# H_Bridge.net
KiCad netlist of a schematic drawn in Altium Designer
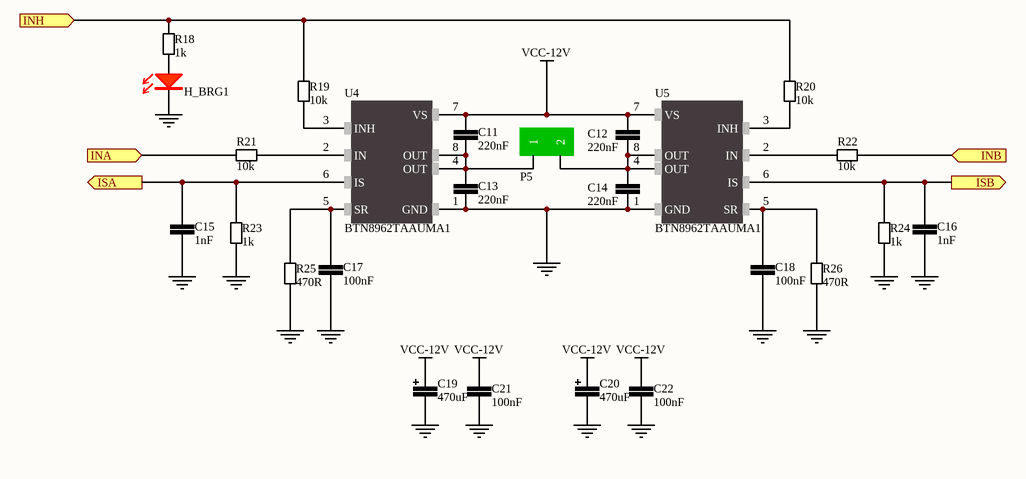
[diagram p0: H_Bridge.SchDoc]

(export (version "E")
  (design (tool "Eeschema 10.0.6"))
  (components
    (comp (ref "C11")
      (value "220nF")
      (footprint "CER_0805")
      (description "CAP CER 220n 10V X5R 10% 0805")
      (libsource (lib "Capacitors") (part "00002205"))
    )
    (comp (ref "C12")
      (value "220nF")
      (footprint "CER_0805")
      (description "CAP CER 220n 10V X5R 10% 0805")
      (libsource (lib "Capacitors") (part "00002205"))
    )
    (comp (ref "C13")
      (value "220nF")
      (footprint "CER_0805")
      (description "CAP CER 220n 10V X5R 10% 0805")
      (libsource (lib "Capacitors") (part "00002205"))
    )
    (comp (ref "C14")
      (value "220nF")
      (footprint "CER_0805")
      (description "CAP CER 220n 10V X5R 10% 0805")
      (libsource (lib "Capacitors") (part "00002205"))
    )
    (comp (ref "C15")
      (value "1nF")
      (footprint "CER_0805")
      (description "CAP CER 1n 50V X7R 10% 0805")
      (libsource (lib "Capacitors") (part "00002105_1"))
    )
    (comp (ref "C16")
      (value "1nF")
      (footprint "CER_0805")
      (description "CAP CER 1n 50V X7R 10% 0805")
      (libsource (lib "Capacitors") (part "00002105_1"))
    )
    (comp (ref "C17")
      (value "100nF")
      (footprint "CER_0805")
      (description "CAP CER 100n 50V X7R 10% 0805")
      (libsource (lib "Capacitors") (part "00002105"))
    )
    (comp (ref "C18")
      (value "100nF")
      (footprint "CER_0805")
      (description "CAP CER 100n 50V X7R 10% 0805")
      (libsource (lib "Capacitors") (part "00002105"))
    )
    (comp (ref "C19")
      (value "470uF")
      (footprint "CAP10X20_RADIAL")
      (description "CAP ALU 470u 25V 20%")
      (libsource (lib "Capacitors") (part "00004707"))
    )
    (comp (ref "C20")
      (value "470uF")
      (footprint "CAP10X20_RADIAL")
      (description "CAP ALU 470u 25V 20%")
      (libsource (lib "Capacitors") (part "00004707"))
    )
    (comp (ref "C21")
      (value "100nF")
      (footprint "CER_0805")
      (description "CAP CER 100n 50V X7R 10% 0805")
      (libsource (lib "Capacitors") (part "00002105"))
    )
    (comp (ref "C22")
      (value "100nF")
      (footprint "CER_0805")
      (description "CAP CER 100n 50V X7R 10% 0805")
      (libsource (lib "Capacitors") (part "00002105"))
    )
    (comp (ref "H_BRG1")
      (value "LED RED")
      (footprint "LED_RED_0805")
      (description "LED RED 0805")
      (fields
        (field (name "MANUFACTURER") "BRIGHT LED ELECTRONICS")
        (field (name "MANUFACTURER PART NUMBER") "BL-HUB35A-AV-TRB")
      )
      (libsource (lib "Discrete_Semiconductor") (part "LED_RED_0805"))
    )
    (comp (ref "P5")
      (value "*")
      (footprint "Electro_Mechanical:MOTOR_CON")
      (description "CONNECTOR FOR MOTOR OUTPUT")
      (libsource (lib "Electro_Mechanical") (part "MOT_CONN"))
    )
    (comp (ref "R18")
      (value "1k")
      (footprint "RESC2013X38N-0805-NOOVERLAY")
      (description "RES SMD 1 kOhm 1/8W 0805")
      (fields (field (name "POWER") "0.125W, 1/8W"))
      (libsource (lib "Resistors") (part "00001001"))
    )
    (comp (ref "R19")
      (value "10k")
      (footprint "RESC2013X38N-0805-NOOVERLAY")
      (description "RES SMD 10 kOhm 1/8W 0805")
      (libsource (lib "") (part "000001002_1"))
    )
    (comp (ref "R20")
      (value "10k")
      (footprint "RESC2013X38N-0805-NOOVERLAY")
      (description "RES SMD 10 kOhm 1/8W 0805")
      (libsource (lib "") (part "000001002_1"))
    )
    (comp (ref "R21")
      (value "10k")
      (footprint "RESC2013X38N-0805-NOOVERLAY")
      (description "RES SMD 10 kOhm 1/8W 0805")
      (libsource (lib "") (part "000001002_2"))
    )
    (comp (ref "R22")
      (value "10k")
      (footprint "RESC2013X38N-0805-NOOVERLAY")
      (description "RES SMD 10 kOhm 1/8W 0805")
      (libsource (lib "Resistors") (part "000001002"))
    )
    (comp (ref "R23")
      (value "1k")
      (footprint "RESC2013X38N-0805-NOOVERLAY")
      (description "RES SMD 1 kOhm 1/8W 0805")
      (fields (field (name "POWER") "0.125W, 1/8W"))
      (libsource (lib "Resistors") (part "00001001"))
    )
    (comp (ref "R24")
      (value "1k")
      (footprint "RESC2013X38N-0805-NOOVERLAY")
      (description "RES SMD 1 kOhm 1/8W 0805")
      (fields (field (name "POWER") "0.125W, 1/8W"))
      (libsource (lib "Resistors") (part "00001001"))
    )
    (comp (ref "R25")
      (value "470R")
      (footprint "RESC2013X38N-0805-NOOVERLAY")
      (description "RES SMD 470 Ohm 1/8W 0805")
      (fields (field (name "POWER") "0.125W, 1/8W"))
      (libsource (lib "Resistors") (part "00004700"))
    )
    (comp (ref "R26")
      (value "470R")
      (footprint "RESC2013X38N-0805-NOOVERLAY")
      (description "RES SMD 470 Ohm 1/8W 0805")
      (fields (field (name "POWER") "0.125W, 1/8W"))
      (libsource (lib "Resistors") (part "00004700"))
    )
    (comp (ref "U4")
      (value "BTN8962TAAUMA1")
      (footprint "TO263-7")
      (description "IC MOTOR DRIVER PAR TO263-7")
      (libsource (lib "") (part "00000010_1"))
    )
    (comp (ref "U5")
      (value "BTN8962TAAUMA1")
      (footprint "TO263-7")
      (description "IC MOTOR DRIVER PAR TO263-7")
      (libsource (lib "Integrated_circuits") (part "00000010"))
    )
  )
  (nets
    (net (code "1") (name "/INA") (class "Default")
      (node (ref "R21") (pin "2") (pinfunction "2_2") (pintype "passive"))
    )
    (net (code "2") (name "/INB") (class "Default")
      (node (ref "R22") (pin "2") (pinfunction "2_2") (pintype "passive"))
    )
    (net (code "3") (name "/INH") (class "Default")
      (node (ref "R18") (pin "2") (pinfunction "2_2") (pintype "passive"))
      (node (ref "R19") (pin "2") (pinfunction "2_2") (pintype "passive"))
      (node (ref "R20") (pin "2") (pinfunction "2_2") (pintype "passive"))
    )
    (net (code "4") (name "/ISA") (class "Default")
      (node (ref "C15") (pin "2") (pinfunction "2_2") (pintype "passive"))
      (node (ref "R23") (pin "2") (pinfunction "2_2") (pintype "passive"))
      (node (ref "U4") (pin "6") (pinfunction "IS_6") (pintype "passive"))
    )
    (net (code "5") (name "/ISB") (class "Default")
      (node (ref "C16") (pin "2") (pinfunction "2_2") (pintype "passive"))
      (node (ref "R24") (pin "2") (pinfunction "2_2") (pintype "passive"))
      (node (ref "U5") (pin "6") (pinfunction "IS_6") (pintype "passive"))
    )
    (net (code "6") (name "GND") (class "Default")
      (node (ref "C13") (pin "1") (pinfunction "1_1") (pintype "passive"))
      (node (ref "C14") (pin "1") (pinfunction "1_1") (pintype "passive"))
      (node (ref "C15") (pin "1") (pinfunction "1_1") (pintype "passive"))
      (node (ref "C16") (pin "1") (pinfunction "1_1") (pintype "passive"))
      (node (ref "C17") (pin "1") (pinfunction "1_1") (pintype "passive"))
      (node (ref "C18") (pin "1") (pinfunction "1_1") (pintype "passive"))
      (node (ref "C19") (pin "2") (pinfunction "2_2") (pintype "passive"))
      (node (ref "C20") (pin "2") (pinfunction "2_2") (pintype "passive"))
      (node (ref "C21") (pin "1") (pinfunction "1_1") (pintype "passive"))
      (node (ref "C22") (pin "1") (pinfunction "1_1") (pintype "passive"))
      (node (ref "H_BRG1") (pin "1") (pinfunction "C_1") (pintype "passive"))
      (node (ref "R23") (pin "1") (pinfunction "1_1") (pintype "passive"))
      (node (ref "R24") (pin "1") (pinfunction "1_1") (pintype "passive"))
      (node (ref "R25") (pin "1") (pinfunction "1_1") (pintype "passive"))
      (node (ref "R26") (pin "1") (pinfunction "1_1") (pintype "passive"))
      (node (ref "U4") (pin "1") (pinfunction "GND_1") (pintype "passive"))
      (node (ref "U5") (pin "1") (pinfunction "GND_1") (pintype "passive"))
    )
    (net (code "7") (name "Net-(C11-Pad1)") (class "Default")
      (node (ref "C11") (pin "1") (pinfunction "1_1") (pintype "passive"))
      (node (ref "C13") (pin "2") (pinfunction "2_2") (pintype "passive"))
      (node (ref "P5") (pin "1") (pinfunction "1_1") (pintype "passive"))
      (node (ref "U4") (pin "4") (pinfunction "OUT_4") (pintype "passive"))
      (node (ref "U4") (pin "8") (pinfunction "OUT_8") (pintype "passive"))
    )
    (net (code "8") (name "Net-(C12-Pad2)") (class "Default")
      (node (ref "C12") (pin "2") (pinfunction "2_2") (pintype "passive"))
      (node (ref "C14") (pin "2") (pinfunction "2_2") (pintype "passive"))
      (node (ref "P5") (pin "2") (pinfunction "2_2") (pintype "passive"))
      (node (ref "U5") (pin "4") (pinfunction "OUT_4") (pintype "passive"))
      (node (ref "U5") (pin "8") (pinfunction "OUT_8") (pintype "passive"))
    )
    (net (code "9") (name "Net-(H_BRG1-A)") (class "Default")
      (node (ref "H_BRG1") (pin "2") (pinfunction "A_2") (pintype "passive"))
      (node (ref "R18") (pin "1") (pinfunction "1_1") (pintype "passive"))
    )
    (net (code "10") (name "Net-(U4-IN)") (class "Default")
      (node (ref "R21") (pin "1") (pinfunction "1_1") (pintype "passive"))
      (node (ref "U4") (pin "2") (pinfunction "IN_2") (pintype "passive"))
    )
    (net (code "11") (name "Net-(U4-INH)") (class "Default")
      (node (ref "R19") (pin "1") (pinfunction "1_1") (pintype "passive"))
      (node (ref "U4") (pin "3") (pinfunction "INH_3") (pintype "passive"))
    )
    (net (code "12") (name "Net-(U4-SR)") (class "Default")
      (node (ref "C17") (pin "2") (pinfunction "2_2") (pintype "passive"))
      (node (ref "R25") (pin "2") (pinfunction "2_2") (pintype "passive"))
      (node (ref "U4") (pin "5") (pinfunction "SR_5") (pintype "passive"))
    )
    (net (code "13") (name "Net-(U5-IN)") (class "Default")
      (node (ref "R22") (pin "1") (pinfunction "1_1") (pintype "passive"))
      (node (ref "U5") (pin "2") (pinfunction "IN_2") (pintype "passive"))
    )
    (net (code "14") (name "Net-(U5-INH)") (class "Default")
      (node (ref "R20") (pin "1") (pinfunction "1_1") (pintype "passive"))
      (node (ref "U5") (pin "3") (pinfunction "INH_3") (pintype "passive"))
    )
    (net (code "15") (name "Net-(U5-SR)") (class "Default")
      (node (ref "C18") (pin "2") (pinfunction "2_2") (pintype "passive"))
      (node (ref "R26") (pin "2") (pinfunction "2_2") (pintype "passive"))
      (node (ref "U5") (pin "5") (pinfunction "SR_5") (pintype "passive"))
    )
    (net (code "16") (name "VCC-12V") (class "Default")
      (node (ref "C11") (pin "2") (pinfunction "2_2") (pintype "passive"))
      (node (ref "C12") (pin "1") (pinfunction "1_1") (pintype "passive"))
      (node (ref "C19") (pin "1") (pinfunction "1_1") (pintype "passive"))
      (node (ref "C20") (pin "1") (pinfunction "1_1") (pintype "passive"))
      (node (ref "C21") (pin "2") (pinfunction "2_2") (pintype "passive"))
      (node (ref "C22") (pin "2") (pinfunction "2_2") (pintype "passive"))
      (node (ref "U4") (pin "7") (pinfunction "VS_7") (pintype "passive"))
      (node (ref "U5") (pin "7") (pinfunction "VS_7") (pintype "passive"))
    )
  )
)
